# placaLeandro2.net
KiCad netlist of a schematic drawn in EAGLE
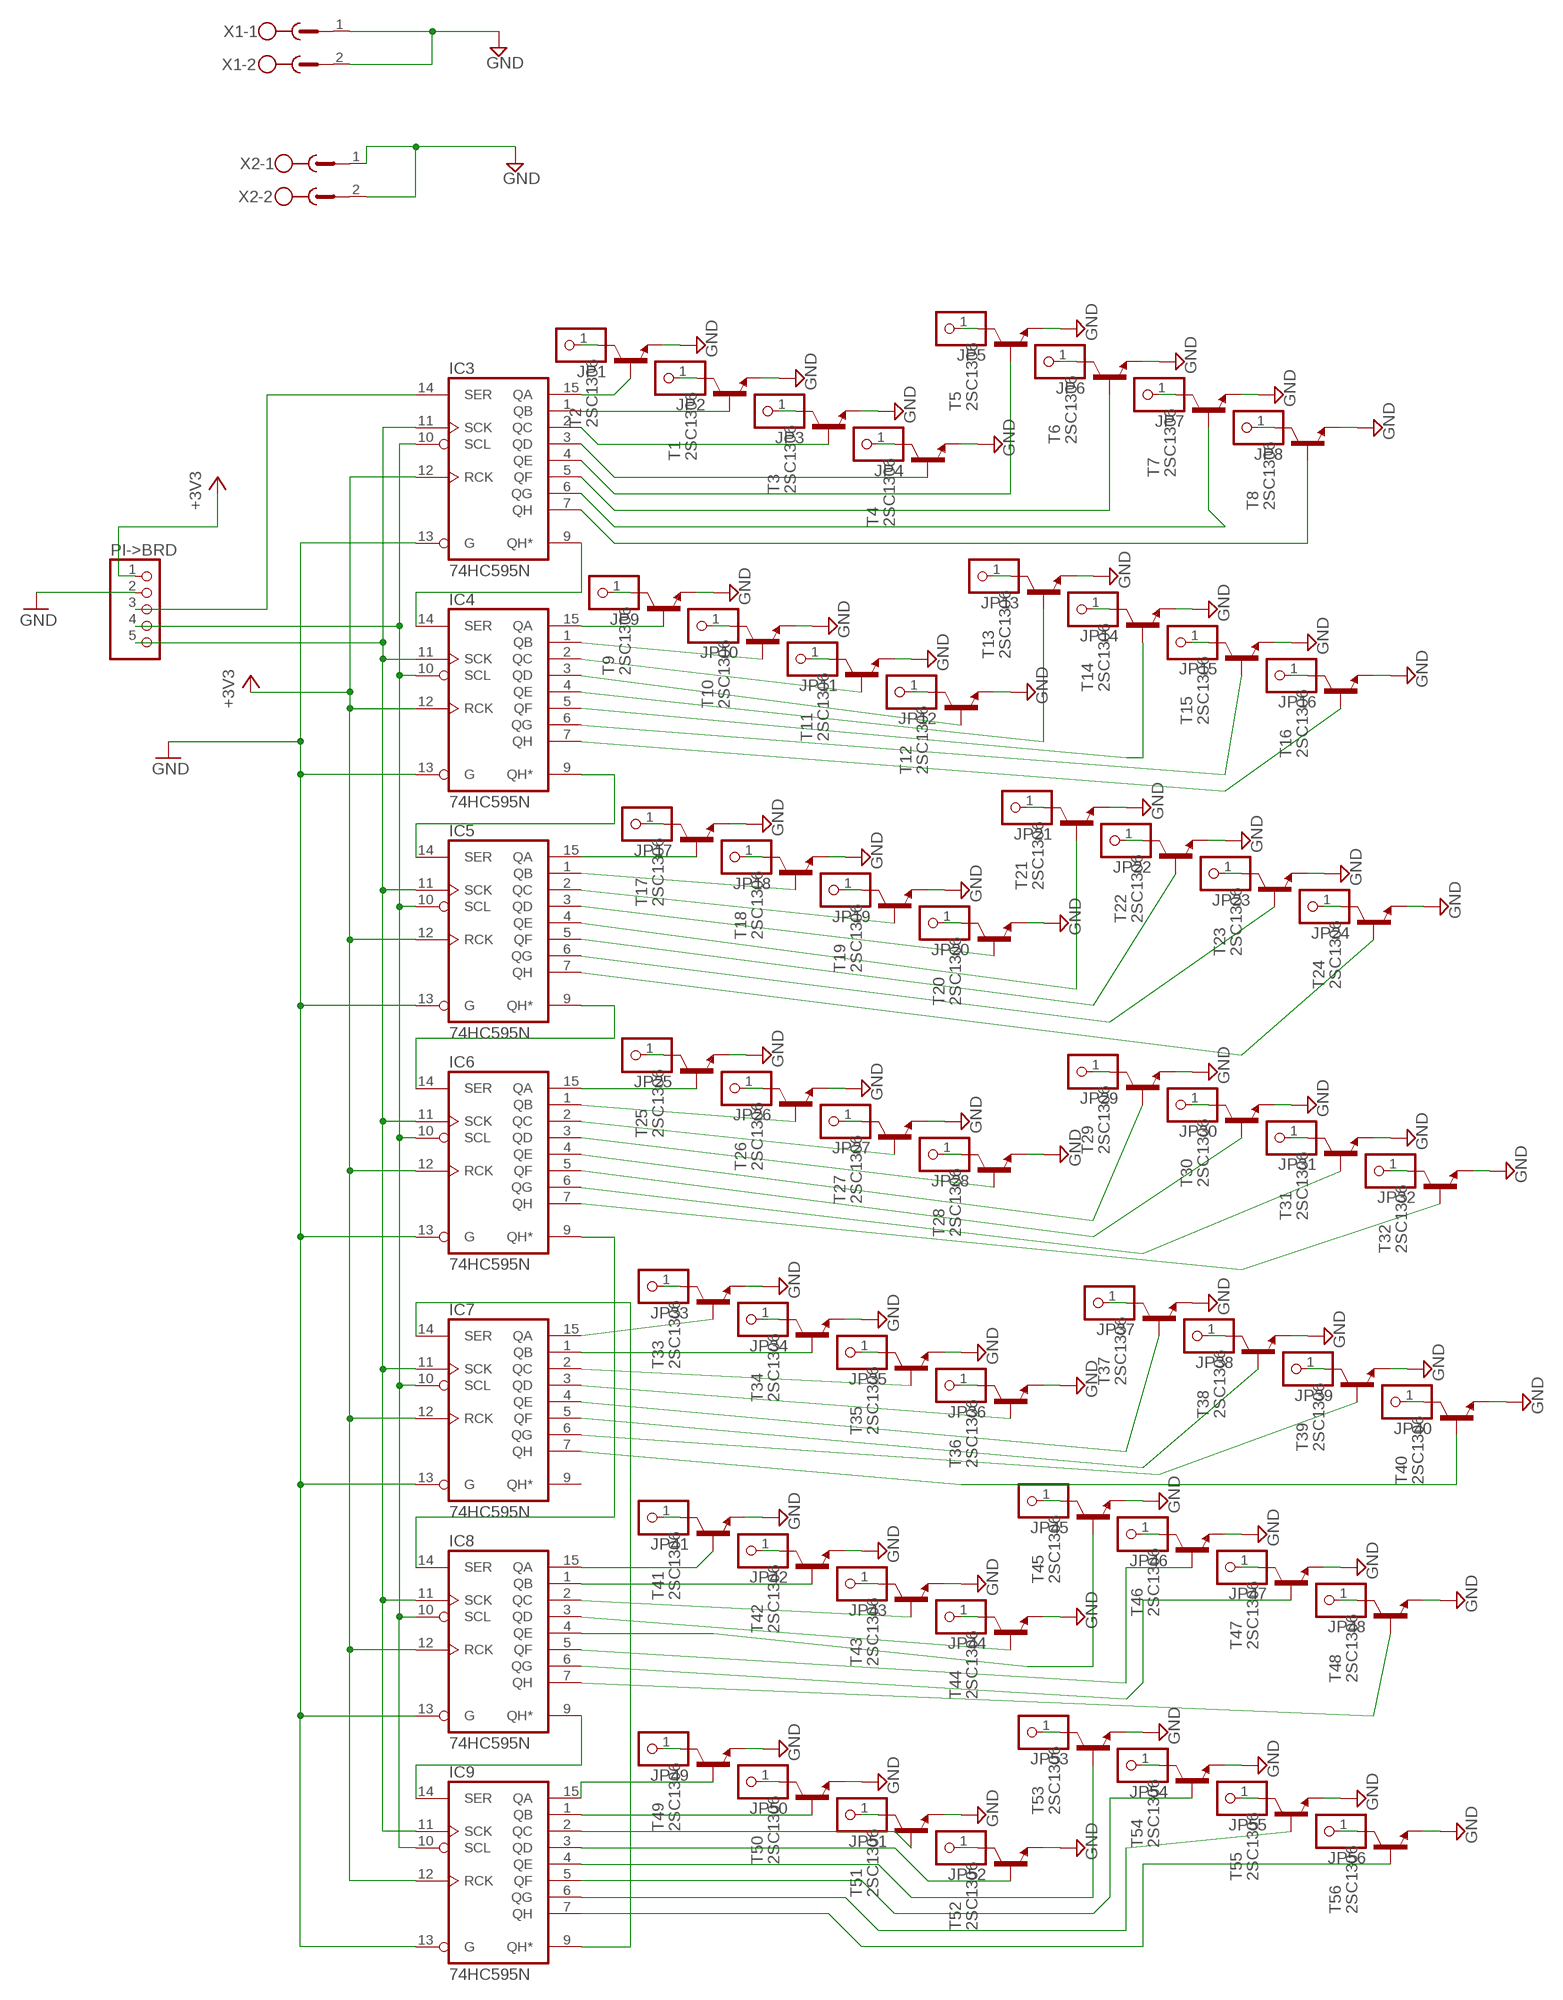
[diagram p0: schematic, sheet 1]

(export (version "E")
  (design (tool "Eeschema 10.0.6"))
  (components
    (comp (ref "IC3")
      (value "74HC595N")
      (footprint "eagle-import:DIL16")
      (libsource (lib "eagle-import") (part "74595NHC"))
    )
    (comp (ref "IC4")
      (value "74HC595N")
      (footprint "eagle-import:DIL16")
      (libsource (lib "eagle-import") (part "74595NHC"))
    )
    (comp (ref "IC5")
      (value "74HC595N")
      (footprint "eagle-import:DIL16")
      (libsource (lib "eagle-import") (part "74595NHC"))
    )
    (comp (ref "IC6")
      (value "74HC595N")
      (footprint "eagle-import:DIL16")
      (libsource (lib "eagle-import") (part "74595NHC"))
    )
    (comp (ref "IC7")
      (value "74HC595N")
      (footprint "eagle-import:DIL16")
      (libsource (lib "eagle-import") (part "74595NHC"))
    )
    (comp (ref "IC8")
      (value "74HC595N")
      (footprint "eagle-import:DIL16")
      (libsource (lib "eagle-import") (part "74595NHC"))
    )
    (comp (ref "IC9")
      (value "74HC595N")
      (footprint "eagle-import:DIL16")
      (libsource (lib "eagle-import") (part "74595NHC"))
    )
    (comp (ref "JP1")
      (value "PINHD-1X1")
      (footprint "eagle-import:1X01")
      (libsource (lib "eagle-import") (part "PINHD-1X1"))
    )
    (comp (ref "JP2")
      (value "PINHD-1X1")
      (footprint "eagle-import:1X01")
      (libsource (lib "eagle-import") (part "PINHD-1X1"))
    )
    (comp (ref "JP3")
      (value "PINHD-1X1")
      (footprint "eagle-import:1X01")
      (libsource (lib "eagle-import") (part "PINHD-1X1"))
    )
    (comp (ref "JP4")
      (value "PINHD-1X1")
      (footprint "eagle-import:1X01")
      (libsource (lib "eagle-import") (part "PINHD-1X1"))
    )
    (comp (ref "JP5")
      (value "PINHD-1X1")
      (footprint "eagle-import:1X01")
      (libsource (lib "eagle-import") (part "PINHD-1X1"))
    )
    (comp (ref "JP6")
      (value "PINHD-1X1")
      (footprint "eagle-import:1X01")
      (libsource (lib "eagle-import") (part "PINHD-1X1"))
    )
    (comp (ref "JP7")
      (value "PINHD-1X1")
      (footprint "eagle-import:1X01")
      (libsource (lib "eagle-import") (part "PINHD-1X1"))
    )
    (comp (ref "JP8")
      (value "PINHD-1X1")
      (footprint "eagle-import:1X01")
      (libsource (lib "eagle-import") (part "PINHD-1X1"))
    )
    (comp (ref "JP9")
      (value "PINHD-1X1")
      (footprint "eagle-import:1X01")
      (libsource (lib "eagle-import") (part "PINHD-1X1"))
    )
    (comp (ref "JP10")
      (value "PINHD-1X1")
      (footprint "eagle-import:1X01")
      (libsource (lib "eagle-import") (part "PINHD-1X1"))
    )
    (comp (ref "JP11")
      (value "PINHD-1X1")
      (footprint "eagle-import:1X01")
      (libsource (lib "eagle-import") (part "PINHD-1X1"))
    )
    (comp (ref "JP12")
      (value "PINHD-1X1")
      (footprint "eagle-import:1X01")
      (libsource (lib "eagle-import") (part "PINHD-1X1"))
    )
    (comp (ref "JP13")
      (value "PINHD-1X1")
      (footprint "eagle-import:1X01")
      (libsource (lib "eagle-import") (part "PINHD-1X1"))
    )
    (comp (ref "JP14")
      (value "PINHD-1X1")
      (footprint "eagle-import:1X01")
      (libsource (lib "eagle-import") (part "PINHD-1X1"))
    )
    (comp (ref "JP15")
      (value "PINHD-1X1")
      (footprint "eagle-import:1X01")
      (libsource (lib "eagle-import") (part "PINHD-1X1"))
    )
    (comp (ref "JP16")
      (value "PINHD-1X1")
      (footprint "eagle-import:1X01")
      (libsource (lib "eagle-import") (part "PINHD-1X1"))
    )
    (comp (ref "JP17")
      (value "PINHD-1X1")
      (footprint "eagle-import:1X01")
      (libsource (lib "eagle-import") (part "PINHD-1X1"))
    )
    (comp (ref "JP18")
      (value "PINHD-1X1")
      (footprint "eagle-import:1X01")
      (libsource (lib "eagle-import") (part "PINHD-1X1"))
    )
    (comp (ref "JP19")
      (value "PINHD-1X1")
      (footprint "eagle-import:1X01")
      (libsource (lib "eagle-import") (part "PINHD-1X1"))
    )
    (comp (ref "JP20")
      (value "PINHD-1X1")
      (footprint "eagle-import:1X01")
      (libsource (lib "eagle-import") (part "PINHD-1X1"))
    )
    (comp (ref "JP21")
      (value "PINHD-1X1")
      (footprint "eagle-import:1X01")
      (libsource (lib "eagle-import") (part "PINHD-1X1"))
    )
    (comp (ref "JP22")
      (value "PINHD-1X1")
      (footprint "eagle-import:1X01")
      (libsource (lib "eagle-import") (part "PINHD-1X1"))
    )
    (comp (ref "JP23")
      (value "PINHD-1X1")
      (footprint "eagle-import:1X01")
      (libsource (lib "eagle-import") (part "PINHD-1X1"))
    )
    (comp (ref "JP24")
      (value "PINHD-1X1")
      (footprint "eagle-import:1X01")
      (libsource (lib "eagle-import") (part "PINHD-1X1"))
    )
    (comp (ref "JP25")
      (value "PINHD-1X1")
      (footprint "eagle-import:1X01")
      (libsource (lib "eagle-import") (part "PINHD-1X1"))
    )
    (comp (ref "JP26")
      (value "PINHD-1X1")
      (footprint "eagle-import:1X01")
      (libsource (lib "eagle-import") (part "PINHD-1X1"))
    )
    (comp (ref "JP27")
      (value "PINHD-1X1")
      (footprint "eagle-import:1X01")
      (libsource (lib "eagle-import") (part "PINHD-1X1"))
    )
    (comp (ref "JP28")
      (value "PINHD-1X1")
      (footprint "eagle-import:1X01")
      (libsource (lib "eagle-import") (part "PINHD-1X1"))
    )
    (comp (ref "JP29")
      (value "PINHD-1X1")
      (footprint "eagle-import:1X01")
      (libsource (lib "eagle-import") (part "PINHD-1X1"))
    )
    (comp (ref "JP30")
      (value "PINHD-1X1")
      (footprint "eagle-import:1X01")
      (libsource (lib "eagle-import") (part "PINHD-1X1"))
    )
    (comp (ref "JP31")
      (value "PINHD-1X1")
      (footprint "eagle-import:1X01")
      (libsource (lib "eagle-import") (part "PINHD-1X1"))
    )
    (comp (ref "JP32")
      (value "PINHD-1X1")
      (footprint "eagle-import:1X01")
      (libsource (lib "eagle-import") (part "PINHD-1X1"))
    )
    (comp (ref "JP33")
      (value "PINHD-1X1")
      (footprint "eagle-import:1X01")
      (libsource (lib "eagle-import") (part "PINHD-1X1"))
    )
    (comp (ref "JP34")
      (value "PINHD-1X1")
      (footprint "eagle-import:1X01")
      (libsource (lib "eagle-import") (part "PINHD-1X1"))
    )
    (comp (ref "JP35")
      (value "PINHD-1X1")
      (footprint "eagle-import:1X01")
      (libsource (lib "eagle-import") (part "PINHD-1X1"))
    )
    (comp (ref "JP36")
      (value "PINHD-1X1")
      (footprint "eagle-import:1X01")
      (libsource (lib "eagle-import") (part "PINHD-1X1"))
    )
    (comp (ref "JP37")
      (value "PINHD-1X1")
      (footprint "eagle-import:1X01")
      (libsource (lib "eagle-import") (part "PINHD-1X1"))
    )
    (comp (ref "JP38")
      (value "PINHD-1X1")
      (footprint "eagle-import:1X01")
      (libsource (lib "eagle-import") (part "PINHD-1X1"))
    )
    (comp (ref "JP39")
      (value "PINHD-1X1")
      (footprint "eagle-import:1X01")
      (libsource (lib "eagle-import") (part "PINHD-1X1"))
    )
    (comp (ref "JP40")
      (value "PINHD-1X1")
      (footprint "eagle-import:1X01")
      (libsource (lib "eagle-import") (part "PINHD-1X1"))
    )
    (comp (ref "JP41")
      (value "PINHD-1X1")
      (footprint "eagle-import:1X01")
      (libsource (lib "eagle-import") (part "PINHD-1X1"))
    )
    (comp (ref "JP42")
      (value "PINHD-1X1")
      (footprint "eagle-import:1X01")
      (libsource (lib "eagle-import") (part "PINHD-1X1"))
    )
    (comp (ref "JP43")
      (value "PINHD-1X1")
      (footprint "eagle-import:1X01")
      (libsource (lib "eagle-import") (part "PINHD-1X1"))
    )
    (comp (ref "JP44")
      (value "PINHD-1X1")
      (footprint "eagle-import:1X01")
      (libsource (lib "eagle-import") (part "PINHD-1X1"))
    )
    (comp (ref "JP45")
      (value "PINHD-1X1")
      (footprint "eagle-import:1X01")
      (libsource (lib "eagle-import") (part "PINHD-1X1"))
    )
    (comp (ref "JP46")
      (value "PINHD-1X1")
      (footprint "eagle-import:1X01")
      (libsource (lib "eagle-import") (part "PINHD-1X1"))
    )
    (comp (ref "JP47")
      (value "PINHD-1X1")
      (footprint "eagle-import:1X01")
      (libsource (lib "eagle-import") (part "PINHD-1X1"))
    )
    (comp (ref "JP48")
      (value "PINHD-1X1")
      (footprint "eagle-import:1X01")
      (libsource (lib "eagle-import") (part "PINHD-1X1"))
    )
    (comp (ref "JP49")
      (value "PINHD-1X1")
      (footprint "eagle-import:1X01")
      (libsource (lib "eagle-import") (part "PINHD-1X1"))
    )
    (comp (ref "JP50")
      (value "PINHD-1X1")
      (footprint "eagle-import:1X01")
      (libsource (lib "eagle-import") (part "PINHD-1X1"))
    )
    (comp (ref "JP51")
      (value "PINHD-1X1")
      (footprint "eagle-import:1X01")
      (libsource (lib "eagle-import") (part "PINHD-1X1"))
    )
    (comp (ref "JP52")
      (value "PINHD-1X1")
      (footprint "eagle-import:1X01")
      (libsource (lib "eagle-import") (part "PINHD-1X1"))
    )
    (comp (ref "JP53")
      (value "PINHD-1X1")
      (footprint "eagle-import:1X01")
      (libsource (lib "eagle-import") (part "PINHD-1X1"))
    )
    (comp (ref "JP54")
      (value "PINHD-1X1")
      (footprint "eagle-import:1X01")
      (libsource (lib "eagle-import") (part "PINHD-1X1"))
    )
    (comp (ref "JP55")
      (value "PINHD-1X1")
      (footprint "eagle-import:1X01")
      (libsource (lib "eagle-import") (part "PINHD-1X1"))
    )
    (comp (ref "JP56")
      (value "PINHD-1X1")
      (footprint "eagle-import:1X01")
      (libsource (lib "eagle-import") (part "PINHD-1X1"))
    )
    (comp (ref "PI->BRD")
      (value "PINHD-1X5")
      (footprint "eagle-import:1X05")
      (libsource (lib "eagle-import") (part "PINHD-1X5"))
    )
    (comp (ref "T1")
      (value "2SC1306")
      (footprint "eagle-import:TO220BV")
      (libsource (lib "eagle-import") (part "2SC1306"))
    )
    (comp (ref "T2")
      (value "2SC1306")
      (footprint "eagle-import:TO220BV")
      (libsource (lib "eagle-import") (part "2SC1306"))
    )
    (comp (ref "T3")
      (value "2SC1306")
      (footprint "eagle-import:TO220BV")
      (libsource (lib "eagle-import") (part "2SC1306"))
    )
    (comp (ref "T4")
      (value "2SC1306")
      (footprint "eagle-import:TO220BV")
      (libsource (lib "eagle-import") (part "2SC1306"))
    )
    (comp (ref "T5")
      (value "2SC1306")
      (footprint "eagle-import:TO220BV")
      (libsource (lib "eagle-import") (part "2SC1306"))
    )
    (comp (ref "T6")
      (value "2SC1306")
      (footprint "eagle-import:TO220BV")
      (libsource (lib "eagle-import") (part "2SC1306"))
    )
    (comp (ref "T7")
      (value "2SC1306")
      (footprint "eagle-import:TO220BV")
      (libsource (lib "eagle-import") (part "2SC1306"))
    )
    (comp (ref "T8")
      (value "2SC1306")
      (footprint "eagle-import:TO220BV")
      (libsource (lib "eagle-import") (part "2SC1306"))
    )
    (comp (ref "T9")
      (value "2SC1306")
      (footprint "eagle-import:TO220BV")
      (libsource (lib "eagle-import") (part "2SC1306"))
    )
    (comp (ref "T10")
      (value "2SC1306")
      (footprint "eagle-import:TO220BV")
      (libsource (lib "eagle-import") (part "2SC1306"))
    )
    (comp (ref "T11")
      (value "2SC1306")
      (footprint "eagle-import:TO220BV")
      (libsource (lib "eagle-import") (part "2SC1306"))
    )
    (comp (ref "T12")
      (value "2SC1306")
      (footprint "eagle-import:TO220BV")
      (libsource (lib "eagle-import") (part "2SC1306"))
    )
    (comp (ref "T13")
      (value "2SC1306")
      (footprint "eagle-import:TO220BV")
      (libsource (lib "eagle-import") (part "2SC1306"))
    )
    (comp (ref "T14")
      (value "2SC1306")
      (footprint "eagle-import:TO220BV")
      (libsource (lib "eagle-import") (part "2SC1306"))
    )
    (comp (ref "T15")
      (value "2SC1306")
      (footprint "eagle-import:TO220BV")
      (libsource (lib "eagle-import") (part "2SC1306"))
    )
    (comp (ref "T16")
      (value "2SC1306")
      (footprint "eagle-import:TO220BV")
      (libsource (lib "eagle-import") (part "2SC1306"))
    )
    (comp (ref "T17")
      (value "2SC1306")
      (footprint "eagle-import:TO220BV")
      (libsource (lib "eagle-import") (part "2SC1306"))
    )
    (comp (ref "T18")
      (value "2SC1306")
      (footprint "eagle-import:TO220BV")
      (libsource (lib "eagle-import") (part "2SC1306"))
    )
    (comp (ref "T19")
      (value "2SC1306")
      (footprint "eagle-import:TO220BV")
      (libsource (lib "eagle-import") (part "2SC1306"))
    )
    (comp (ref "T20")
      (value "2SC1306")
      (footprint "eagle-import:TO220BV")
      (libsource (lib "eagle-import") (part "2SC1306"))
    )
    (comp (ref "T21")
      (value "2SC1306")
      (footprint "eagle-import:TO220BV")
      (libsource (lib "eagle-import") (part "2SC1306"))
    )
    (comp (ref "T22")
      (value "2SC1306")
      (footprint "eagle-import:TO220BV")
      (libsource (lib "eagle-import") (part "2SC1306"))
    )
    (comp (ref "T23")
      (value "2SC1306")
      (footprint "eagle-import:TO220BV")
      (libsource (lib "eagle-import") (part "2SC1306"))
    )
    (comp (ref "T24")
      (value "2SC1306")
      (footprint "eagle-import:TO220BV")
      (libsource (lib "eagle-import") (part "2SC1306"))
    )
    (comp (ref "T25")
      (value "2SC1306")
      (footprint "eagle-import:TO220BV")
      (libsource (lib "eagle-import") (part "2SC1306"))
    )
    (comp (ref "T26")
      (value "2SC1306")
      (footprint "eagle-import:TO220BV")
      (libsource (lib "eagle-import") (part "2SC1306"))
    )
    (comp (ref "T27")
      (value "2SC1306")
      (footprint "eagle-import:TO220BV")
      (libsource (lib "eagle-import") (part "2SC1306"))
    )
    (comp (ref "T28")
      (value "2SC1306")
      (footprint "eagle-import:TO220BV")
      (libsource (lib "eagle-import") (part "2SC1306"))
    )
    (comp (ref "T29")
      (value "2SC1306")
      (footprint "eagle-import:TO220BV")
      (libsource (lib "eagle-import") (part "2SC1306"))
    )
    (comp (ref "T30")
      (value "2SC1306")
      (footprint "eagle-import:TO220BV")
      (libsource (lib "eagle-import") (part "2SC1306"))
    )
    (comp (ref "T31")
      (value "2SC1306")
      (footprint "eagle-import:TO220BV")
      (libsource (lib "eagle-import") (part "2SC1306"))
    )
    (comp (ref "T32")
      (value "2SC1306")
      (footprint "eagle-import:TO220BV")
      (libsource (lib "eagle-import") (part "2SC1306"))
    )
    (comp (ref "T33")
      (value "2SC1306")
      (footprint "eagle-import:TO220BV")
      (libsource (lib "eagle-import") (part "2SC1306"))
    )
    (comp (ref "T34")
      (value "2SC1306")
      (footprint "eagle-import:TO220BV")
      (libsource (lib "eagle-import") (part "2SC1306"))
    )
    (comp (ref "T35")
      (value "2SC1306")
      (footprint "eagle-import:TO220BV")
      (libsource (lib "eagle-import") (part "2SC1306"))
    )
    (comp (ref "T36")
      (value "2SC1306")
      (footprint "eagle-import:TO220BV")
      (libsource (lib "eagle-import") (part "2SC1306"))
    )
    (comp (ref "T37")
      (value "2SC1306")
      (footprint "eagle-import:TO220BV")
      (libsource (lib "eagle-import") (part "2SC1306"))
    )
    (comp (ref "T38")
      (value "2SC1306")
      (footprint "eagle-import:TO220BV")
      (libsource (lib "eagle-import") (part "2SC1306"))
    )
    (comp (ref "T39")
      (value "2SC1306")
      (footprint "eagle-import:TO220BV")
      (libsource (lib "eagle-import") (part "2SC1306"))
    )
    (comp (ref "T40")
      (value "2SC1306")
      (footprint "eagle-import:TO220BV")
      (libsource (lib "eagle-import") (part "2SC1306"))
    )
    (comp (ref "T41")
      (value "2SC1306")
      (footprint "eagle-import:TO220BV")
      (libsource (lib "eagle-import") (part "2SC1306"))
    )
    (comp (ref "T42")
      (value "2SC1306")
      (footprint "eagle-import:TO220BV")
      (libsource (lib "eagle-import") (part "2SC1306"))
    )
    (comp (ref "T43")
      (value "2SC1306")
      (footprint "eagle-import:TO220BV")
      (libsource (lib "eagle-import") (part "2SC1306"))
    )
    (comp (ref "T44")
      (value "2SC1306")
      (footprint "eagle-import:TO220BV")
      (libsource (lib "eagle-import") (part "2SC1306"))
    )
    (comp (ref "T45")
      (value "2SC1306")
      (footprint "eagle-import:TO220BV")
      (libsource (lib "eagle-import") (part "2SC1306"))
    )
    (comp (ref "T46")
      (value "2SC1306")
      (footprint "eagle-import:TO220BV")
      (libsource (lib "eagle-import") (part "2SC1306"))
    )
    (comp (ref "T47")
      (value "2SC1306")
      (footprint "eagle-import:TO220BV")
      (libsource (lib "eagle-import") (part "2SC1306"))
    )
    (comp (ref "T48")
      (value "2SC1306")
      (footprint "eagle-import:TO220BV")
      (libsource (lib "eagle-import") (part "2SC1306"))
    )
    (comp (ref "T49")
      (value "2SC1306")
      (footprint "eagle-import:TO220BV")
      (libsource (lib "eagle-import") (part "2SC1306"))
    )
    (comp (ref "T50")
      (value "2SC1306")
      (footprint "eagle-import:TO220BV")
      (libsource (lib "eagle-import") (part "2SC1306"))
    )
    (comp (ref "T51")
      (value "2SC1306")
      (footprint "eagle-import:TO220BV")
      (libsource (lib "eagle-import") (part "2SC1306"))
    )
    (comp (ref "T52")
      (value "2SC1306")
      (footprint "eagle-import:TO220BV")
      (libsource (lib "eagle-import") (part "2SC1306"))
    )
    (comp (ref "T53")
      (value "2SC1306")
      (footprint "eagle-import:TO220BV")
      (libsource (lib "eagle-import") (part "2SC1306"))
    )
    (comp (ref "T54")
      (value "2SC1306")
      (footprint "eagle-import:TO220BV")
      (libsource (lib "eagle-import") (part "2SC1306"))
    )
    (comp (ref "T55")
      (value "2SC1306")
      (footprint "eagle-import:TO220BV")
      (libsource (lib "eagle-import") (part "2SC1306"))
    )
    (comp (ref "T56")
      (value "2SC1306")
      (footprint "eagle-import:TO220BV")
      (libsource (lib "eagle-import") (part "2SC1306"))
    )
    (comp (ref "X1")
      (value "MSTBV2")
      (footprint "eagle-import:MSTBV2")
      (libsource (lib "eagle-import") (part "MSTBV2"))
    )
    (comp (ref "X2")
      (value "MSTBV2")
      (footprint "eagle-import:MSTBV2")
      (libsource (lib "eagle-import") (part "MSTBV2"))
    )
  )
  (nets
    (net (code "1") (name "+3V3") (class "Default")
      (node (ref "IC3") (pin "12") (pinfunction "RCK_12") (pintype "input"))
      (node (ref "IC4") (pin "12") (pinfunction "RCK_12") (pintype "input"))
      (node (ref "IC5") (pin "12") (pinfunction "RCK_12") (pintype "input"))
      (node (ref "IC6") (pin "12") (pinfunction "RCK_12") (pintype "input"))
      (node (ref "IC7") (pin "12") (pinfunction "RCK_12") (pintype "input"))
      (node (ref "IC8") (pin "12") (pinfunction "RCK_12") (pintype "input"))
      (node (ref "IC9") (pin "12") (pinfunction "RCK_12") (pintype "input"))
      (node (ref "PI->BRD") (pin "1") (pinfunction "1_1") (pintype "passive"))
    )
    (net (code "2") (name "GND") (class "Default")
      (node (ref "IC3") (pin "13") (pinfunction "G_13") (pintype "input"))
      (node (ref "IC4") (pin "13") (pinfunction "G_13") (pintype "input"))
      (node (ref "IC5") (pin "13") (pinfunction "G_13") (pintype "input"))
      (node (ref "IC6") (pin "13") (pinfunction "G_13") (pintype "input"))
      (node (ref "IC7") (pin "13") (pinfunction "G_13") (pintype "input"))
      (node (ref "IC8") (pin "13") (pinfunction "G_13") (pintype "input"))
      (node (ref "IC9") (pin "13") (pinfunction "G_13") (pintype "input"))
      (node (ref "PI->BRD") (pin "2") (pinfunction "2_2") (pintype "passive"))
      (node (ref "T1") (pin "3") (pinfunction "E_3") (pintype "passive"))
      (node (ref "T10") (pin "3") (pinfunction "E_3") (pintype "passive"))
      (node (ref "T11") (pin "3") (pinfunction "E_3") (pintype "passive"))
      (node (ref "T12") (pin "3") (pinfunction "E_3") (pintype "passive"))
      (node (ref "T13") (pin "3") (pinfunction "E_3") (pintype "passive"))
      (node (ref "T14") (pin "3") (pinfunction "E_3") (pintype "passive"))
      (node (ref "T15") (pin "3") (pinfunction "E_3") (pintype "passive"))
      (node (ref "T16") (pin "3") (pinfunction "E_3") (pintype "passive"))
      (node (ref "T17") (pin "3") (pinfunction "E_3") (pintype "passive"))
      (node (ref "T18") (pin "3") (pinfunction "E_3") (pintype "passive"))
      (node (ref "T19") (pin "3") (pinfunction "E_3") (pintype "passive"))
      (node (ref "T2") (pin "3") (pinfunction "E_3") (pintype "passive"))
      (node (ref "T20") (pin "3") (pinfunction "E_3") (pintype "passive"))
      (node (ref "T21") (pin "3") (pinfunction "E_3") (pintype "passive"))
      (node (ref "T22") (pin "3") (pinfunction "E_3") (pintype "passive"))
      (node (ref "T23") (pin "3") (pinfunction "E_3") (pintype "passive"))
      (node (ref "T24") (pin "3") (pinfunction "E_3") (pintype "passive"))
      (node (ref "T25") (pin "3") (pinfunction "E_3") (pintype "passive"))
      (node (ref "T26") (pin "3") (pinfunction "E_3") (pintype "passive"))
      (node (ref "T27") (pin "3") (pinfunction "E_3") (pintype "passive"))
      (node (ref "T28") (pin "3") (pinfunction "E_3") (pintype "passive"))
      (node (ref "T29") (pin "3") (pinfunction "E_3") (pintype "passive"))
      (node (ref "T3") (pin "3") (pinfunction "E_3") (pintype "passive"))
      (node (ref "T30") (pin "3") (pinfunction "E_3") (pintype "passive"))
      (node (ref "T31") (pin "3") (pinfunction "E_3") (pintype "passive"))
      (node (ref "T32") (pin "3") (pinfunction "E_3") (pintype "passive"))
      (node (ref "T33") (pin "3") (pinfunction "E_3") (pintype "passive"))
      (node (ref "T34") (pin "3") (pinfunction "E_3") (pintype "passive"))
      (node (ref "T35") (pin "3") (pinfunction "E_3") (pintype "passive"))
      (node (ref "T36") (pin "3") (pinfunction "E_3") (pintype "passive"))
      (node (ref "T37") (pin "3") (pinfunction "E_3") (pintype "passive"))
      (node (ref "T38") (pin "3") (pinfunction "E_3") (pintype "passive"))
      (node (ref "T39") (pin "3") (pinfunction "E_3") (pintype "passive"))
      (node (ref "T4") (pin "3") (pinfunction "E_3") (pintype "passive"))
      (node (ref "T40") (pin "3") (pinfunction "E_3") (pintype "passive"))
      (node (ref "T41") (pin "3") (pinfunction "E_3") (pintype "passive"))
      (node (ref "T42") (pin "3") (pinfunction "E_3") (pintype "passive"))
      (node (ref "T43") (pin "3") (pinfunction "E_3") (pintype "passive"))
      (node (ref "T44") (pin "3") (pinfunction "E_3") (pintype "passive"))
      (node (ref "T45") (pin "3") (pinfunction "E_3") (pintype "passive"))
      (node (ref "T46") (pin "3") (pinfunction "E_3") (pintype "passive"))
      (node (ref "T47") (pin "3") (pinfunction "E_3") (pintype "passive"))
      (node (ref "T48") (pin "3") (pinfunction "E_3") (pintype "passive"))
      (node (ref "T49") (pin "3") (pinfunction "E_3") (pintype "passive"))
      (node (ref "T5") (pin "3") (pinfunction "E_3") (pintype "passive"))
      (node (ref "T50") (pin "3") (pinfunction "E_3") (pintype "passive"))
      (node (ref "T51") (pin "3") (pinfunction "E_3") (pintype "passive"))
      (node (ref "T52") (pin "3") (pinfunction "E_3") (pintype "passive"))
      (node (ref "T53") (pin "3") (pinfunction "E_3") (pintype "passive"))
      (node (ref "T54") (pin "3") (pinfunction "E_3") (pintype "passive"))
      (node (ref "T55") (pin "3") (pinfunction "E_3") (pintype "passive"))
      (node (ref "T56") (pin "3") (pinfunction "E_3") (pintype "passive"))
      (node (ref "T6") (pin "3") (pinfunction "E_3") (pintype "passive"))
      (node (ref "T7") (pin "3") (pinfunction "E_3") (pintype "passive"))
      (node (ref "T8") (pin "3") (pinfunction "E_3") (pintype "passive"))
      (node (ref "T9") (pin "3") (pinfunction "E_3") (pintype "passive"))
      (node (ref "X1") (pin "1") (pinfunction "SK_1") (pintype "passive"))
      (node (ref "X1") (pin "2") (pinfunction "SK_2") (pintype "passive"))
      (node (ref "X2") (pin "1") (pinfunction "SK_1") (pintype "passive"))
      (node (ref "X2") (pin "2") (pinfunction "SK_2") (pintype "passive"))
    )
    (net (code "3") (name "Net-(IC3A-QA)") (class "Default")
      (node (ref "IC3") (pin "15") (pinfunction "QA_15") (pintype "tri_state"))
      (node (ref "T2") (pin "1") (pinfunction "B_1") (pintype "passive"))
    )
    (net (code "4") (name "Net-(IC3A-QB)") (class "Default")
      (node (ref "IC3") (pin "1") (pinfunction "QB_1") (pintype "tri_state"))
      (node (ref "T1") (pin "1") (pinfunction "B_1") (pintype "passive"))
    )
    (net (code "5") (name "Net-(IC3A-QC)") (class "Default")
      (node (ref "IC3") (pin "2") (pinfunction "QC_2") (pintype "tri_state"))
      (node (ref "T3") (pin "1") (pinfunction "B_1") (pintype "passive"))
    )
    (net (code "6") (name "Net-(IC3A-QD)") (class "Default")
      (node (ref "IC3") (pin "3") (pinfunction "QD_3") (pintype "tri_state"))
      (node (ref "T4") (pin "1") (pinfunction "B_1") (pintype "passive"))
    )
    (net (code "7") (name "Net-(IC3A-QE)") (class "Default")
      (node (ref "IC3") (pin "4") (pinfunction "QE_4") (pintype "tri_state"))
      (node (ref "T5") (pin "1") (pinfunction "B_1") (pintype "passive"))
    )
    (net (code "8") (name "Net-(IC3A-QF)") (class "Default")
      (node (ref "IC3") (pin "5") (pinfunction "QF_5") (pintype "tri_state"))
      (node (ref "T6") (pin "1") (pinfunction "B_1") (pintype "passive"))
    )
    (net (code "9") (name "Net-(IC3A-QG)") (class "Default")
      (node (ref "IC3") (pin "6") (pinfunction "QG_6") (pintype "tri_state"))
      (node (ref "T7") (pin "1") (pinfunction "B_1") (pintype "passive"))
    )
    (net (code "10") (name "Net-(IC3A-QH)") (class "Default")
      (node (ref "IC3") (pin "7") (pinfunction "QH_7") (pintype "tri_state"))
      (node (ref "T8") (pin "1") (pinfunction "B_1") (pintype "passive"))
    )
    (net (code "11") (name "Net-(IC3A-QH*)") (class "Default")
      (node (ref "IC3") (pin "9") (pinfunction "QH*_9") (pintype "tri_state"))
      (node (ref "IC4") (pin "14") (pinfunction "SER_14") (pintype "input"))
    )
    (net (code "12") (name "Net-(IC3A-SCK)") (class "Default")
      (node (ref "IC3") (pin "11") (pinfunction "SCK_11") (pintype "input"))
      (node (ref "IC4") (pin "11") (pinfunction "SCK_11") (pintype "input"))
      (node (ref "IC5") (pin "11") (pinfunction "SCK_11") (pintype "input"))
      (node (ref "IC6") (pin "11") (pinfunction "SCK_11") (pintype "input"))
      (node (ref "IC7") (pin "11") (pinfunction "SCK_11") (pintype "input"))
      (node (ref "IC8") (pin "11") (pinfunction "SCK_11") (pintype "input"))
      (node (ref "IC9") (pin "11") (pinfunction "SCK_11") (pintype "input"))
      (node (ref "PI->BRD") (pin "5") (pinfunction "5_5") (pintype "passive"))
    )
    (net (code "13") (name "Net-(IC3A-SCL)") (class "Default")
      (node (ref "IC3") (pin "10") (pinfunction "SCL_10") (pintype "input"))
      (node (ref "IC4") (pin "10") (pinfunction "SCL_10") (pintype "input"))
      (node (ref "IC5") (pin "10") (pinfunction "SCL_10") (pintype "input"))
      (node (ref "IC6") (pin "10") (pinfunction "SCL_10") (pintype "input"))
      (node (ref "IC7") (pin "10") (pinfunction "SCL_10") (pintype "input"))
      (node (ref "IC8") (pin "10") (pinfunction "SCL_10") (pintype "input"))
      (node (ref "IC9") (pin "10") (pinfunction "SCL_10") (pintype "input"))
      (node (ref "PI->BRD") (pin "4") (pinfunction "4_4") (pintype "passive"))
    )
    (net (code "14") (name "Net-(IC3A-SER)") (class "Default")
      (node (ref "IC3") (pin "14") (pinfunction "SER_14") (pintype "input"))
      (node (ref "PI->BRD") (pin "3") (pinfunction "3_3") (pintype "passive"))
    )
    (net (code "15") (name "Net-(IC4A-QA)") (class "Default")
      (node (ref "IC4") (pin "15") (pinfunction "QA_15") (pintype "tri_state"))
      (node (ref "T9") (pin "1") (pinfunction "B_1") (pintype "passive"))
    )
    (net (code "16") (name "Net-(IC4A-QB)") (class "Default")
      (node (ref "IC4") (pin "1") (pinfunction "QB_1") (pintype "tri_state"))
      (node (ref "T10") (pin "1") (pinfunction "B_1") (pintype "passive"))
    )
    (net (code "17") (name "Net-(IC4A-QC)") (class "Default")
      (node (ref "IC4") (pin "2") (pinfunction "QC_2") (pintype "tri_state"))
      (node (ref "T11") (pin "1") (pinfunction "B_1") (pintype "passive"))
    )
    (net (code "18") (name "Net-(IC4A-QD)") (class "Default")
      (node (ref "IC4") (pin "3") (pinfunction "QD_3") (pintype "tri_state"))
      (node (ref "T12") (pin "1") (pinfunction "B_1") (pintype "passive"))
    )
    (net (code "19") (name "Net-(IC4A-QE)") (class "Default")
      (node (ref "IC4") (pin "4") (pinfunction "QE_4") (pintype "tri_state"))
      (node (ref "T13") (pin "1") (pinfunction "B_1") (pintype "passive"))
    )
    (net (code "20") (name "Net-(IC4A-QF)") (class "Default")
      (node (ref "IC4") (pin "5") (pinfunction "QF_5") (pintype "tri_state"))
      (node (ref "T14") (pin "1") (pinfunction "B_1") (pintype "passive"))
    )
    (net (code "21") (name "Net-(IC4A-QG)") (class "Default")
      (node (ref "IC4") (pin "6") (pinfunction "QG_6") (pintype "tri_state"))
      (node (ref "T15") (pin "1") (pinfunction "B_1") (pintype "passive"))
    )
    (net (code "22") (name "Net-(IC4A-QH)") (class "Default")
      (node (ref "IC4") (pin "7") (pinfunction "QH_7") (pintype "tri_state"))
      (node (ref "T16") (pin "1") (pinfunction "B_1") (pintype "passive"))
    )
    (net (code "23") (name "Net-(IC4A-QH*)") (class "Default")
      (node (ref "IC4") (pin "9") (pinfunction "QH*_9") (pintype "tri_state"))
      (node (ref "IC5") (pin "14") (pinfunction "SER_14") (pintype "input"))
    )
    (net (code "24") (name "Net-(IC5A-QA)") (class "Default")
      (node (ref "IC5") (pin "15") (pinfunction "QA_15") (pintype "tri_state"))
      (node (ref "T17") (pin "1") (pinfunction "B_1") (pintype "passive"))
    )
    (net (code "25") (name "Net-(IC5A-QB)") (class "Default")
      (node (ref "IC5") (pin "1") (pinfunction "QB_1") (pintype "tri_state"))
      (node (ref "T18") (pin "1") (pinfunction "B_1") (pintype "passive"))
    )
    (net (code "26") (name "Net-(IC5A-QC)") (class "Default")
      (node (ref "IC5") (pin "2") (pinfunction "QC_2") (pintype "tri_state"))
      (node (ref "T19") (pin "1") (pinfunction "B_1") (pintype "passive"))
    )
    (net (code "27") (name "Net-(IC5A-QD)") (class "Default")
      (node (ref "IC5") (pin "3") (pinfunction "QD_3") (pintype "tri_state"))
      (node (ref "T20") (pin "1") (pinfunction "B_1") (pintype "passive"))
    )
    (net (code "28") (name "Net-(IC5A-QE)") (class "Default")
      (node (ref "IC5") (pin "4") (pinfunction "QE_4") (pintype "tri_state"))
      (node (ref "T21") (pin "1") (pinfunction "B_1") (pintype "passive"))
    )
    (net (code "29") (name "Net-(IC5A-QF)") (class "Default")
      (node (ref "IC5") (pin "5") (pinfunction "QF_5") (pintype "tri_state"))
      (node (ref "T22") (pin "1") (pinfunction "B_1") (pintype "passive"))
    )
    (net (code "30") (name "Net-(IC5A-QG)") (class "Default")
      (node (ref "IC5") (pin "6") (pinfunction "QG_6") (pintype "tri_state"))
      (node (ref "T23") (pin "1") (pinfunction "B_1") (pintype "passive"))
    )
    (net (code "31") (name "Net-(IC5A-QH)") (class "Default")
      (node (ref "IC5") (pin "7") (pinfunction "QH_7") (pintype "tri_state"))
      (node (ref "T24") (pin "1") (pinfunction "B_1") (pintype "passive"))
    )
    (net (code "32") (name "Net-(IC5A-QH*)") (class "Default")
      (node (ref "IC5") (pin "9") (pinfunction "QH*_9") (pintype "tri_state"))
      (node (ref "IC6") (pin "14") (pinfunction "SER_14") (pintype "input"))
    )
    (net (code "33") (name "Net-(IC6A-QA)") (class "Default")
      (node (ref "IC6") (pin "15") (pinfunction "QA_15") (pintype "tri_state"))
      (node (ref "T25") (pin "1") (pinfunction "B_1") (pintype "passive"))
    )
    (net (code "34") (name "Net-(IC6A-QB)") (class "Default")
      (node (ref "IC6") (pin "1") (pinfunction "QB_1") (pintype "tri_state"))
      (node (ref "T26") (pin "1") (pinfunction "B_1") (pintype "passive"))
    )
    (net (code "35") (name "Net-(IC6A-QC)") (class "Default")
      (node (ref "IC6") (pin "2") (pinfunction "QC_2") (pintype "tri_state"))
      (node (ref "T27") (pin "1") (pinfunction "B_1") (pintype "passive"))
    )
    (net (code "36") (name "Net-(IC6A-QD)") (class "Default")
      (node (ref "IC6") (pin "3") (pinfunction "QD_3") (pintype "tri_state"))
      (node (ref "T28") (pin "1") (pinfunction "B_1") (pintype "passive"))
    )
    (net (code "37") (name "Net-(IC6A-QE)") (class "Default")
      (node (ref "IC6") (pin "4") (pinfunction "QE_4") (pintype "tri_state"))
      (node (ref "T29") (pin "1") (pinfunction "B_1") (pintype "passive"))
    )
    (net (code "38") (name "Net-(IC6A-QF)") (class "Default")
      (node (ref "IC6") (pin "5") (pinfunction "QF_5") (pintype "tri_state"))
      (node (ref "T30") (pin "1") (pinfunction "B_1") (pintype "passive"))
    )
    (net (code "39") (name "Net-(IC6A-QG)") (class "Default")
      (node (ref "IC6") (pin "6") (pinfunction "QG_6") (pintype "tri_state"))
      (node (ref "T31") (pin "1") (pinfunction "B_1") (pintype "passive"))
    )
    (net (code "40") (name "Net-(IC6A-QH)") (class "Default")
      (node (ref "IC6") (pin "7") (pinfunction "QH_7") (pintype "tri_state"))
      (node (ref "T32") (pin "1") (pinfunction "B_1") (pintype "passive"))
    )
    (net (code "41") (name "Net-(IC6A-QH*)") (class "Default")
      (node (ref "IC6") (pin "9") (pinfunction "QH*_9") (pintype "tri_state"))
      (node (ref "IC8") (pin "14") (pinfunction "SER_14") (pintype "input"))
    )
    (net (code "42") (name "Net-(IC7A-QA)") (class "Default")
      (node (ref "IC7") (pin "15") (pinfunction "QA_15") (pintype "tri_state"))
      (node (ref "T33") (pin "1") (pinfunction "B_1") (pintype "passive"))
    )
    (net (code "43") (name "Net-(IC7A-QB)") (class "Default")
      (node (ref "IC7") (pin "1") (pinfunction "QB_1") (pintype "tri_state"))
      (node (ref "T34") (pin "1") (pinfunction "B_1") (pintype "passive"))
    )
    (net (code "44") (name "Net-(IC7A-QC)") (class "Default")
      (node (ref "IC7") (pin "2") (pinfunction "QC_2") (pintype "tri_state"))
      (node (ref "T35") (pin "1") (pinfunction "B_1") (pintype "passive"))
    )
    (net (code "45") (name "Net-(IC7A-QD)") (class "Default")
      (node (ref "IC7") (pin "3") (pinfunction "QD_3") (pintype "tri_state"))
      (node (ref "T36") (pin "1") (pinfunction "B_1") (pintype "passive"))
    )
    (net (code "46") (name "Net-(IC7A-QE)") (class "Default")
      (node (ref "IC7") (pin "4") (pinfunction "QE_4") (pintype "tri_state"))
      (node (ref "T37") (pin "1") (pinfunction "B_1") (pintype "passive"))
    )
    (net (code "47") (name "Net-(IC7A-QF)") (class "Default")
      (node (ref "IC7") (pin "5") (pinfunction "QF_5") (pintype "tri_state"))
      (node (ref "T38") (pin "1") (pinfunction "B_1") (pintype "passive"))
    )
    (net (code "48") (name "Net-(IC7A-QG)") (class "Default")
      (node (ref "IC7") (pin "6") (pinfunction "QG_6") (pintype "tri_state"))
      (node (ref "T39") (pin "1") (pinfunction "B_1") (pintype "passive"))
    )
    (net (code "49") (name "Net-(IC7A-QH)") (class "Default")
      (node (ref "IC7") (pin "7") (pinfunction "QH_7") (pintype "tri_state"))
      (node (ref "T40") (pin "1") (pinfunction "B_1") (pintype "passive"))
    )
    (net (code "50") (name "Net-(IC7A-SER)") (class "Default")
      (node (ref "IC7") (pin "14") (pinfunction "SER_14") (pintype "input"))
      (node (ref "IC9") (pin "9") (pinfunction "QH*_9") (pintype "tri_state"))
    )
    (net (code "51") (name "Net-(IC8A-QA)") (class "Default")
      (node (ref "IC8") (pin "15") (pinfunction "QA_15") (pintype "tri_state"))
      (node (ref "T41") (pin "1") (pinfunction "B_1") (pintype "passive"))
    )
    (net (code "52") (name "Net-(IC8A-QB)") (class "Default")
      (node (ref "IC8") (pin "1") (pinfunction "QB_1") (pintype "tri_state"))
      (node (ref "T42") (pin "1") (pinfunction "B_1") (pintype "passive"))
    )
    (net (code "53") (name "Net-(IC8A-QC)") (class "Default")
      (node (ref "IC8") (pin "2") (pinfunction "QC_2") (pintype "tri_state"))
      (node (ref "T43") (pin "1") (pinfunction "B_1") (pintype "passive"))
    )
    (net (code "54") (name "Net-(IC8A-QD)") (class "Default")
      (node (ref "IC8") (pin "3") (pinfunction "QD_3") (pintype "tri_state"))
      (node (ref "T44") (pin "1") (pinfunction "B_1") (pintype "passive"))
    )
    (net (code "55") (name "Net-(IC8A-QE)") (class "Default")
      (node (ref "IC8") (pin "4") (pinfunction "QE_4") (pintype "tri_state"))
      (node (ref "T45") (pin "1") (pinfunction "B_1") (pintype "passive"))
    )
    (net (code "56") (name "Net-(IC8A-QF)") (class "Default")
      (node (ref "IC8") (pin "5") (pinfunction "QF_5") (pintype "tri_state"))
      (node (ref "T46") (pin "1") (pinfunction "B_1") (pintype "passive"))
    )
    (net (code "57") (name "Net-(IC8A-QG)") (class "Default")
      (node (ref "IC8") (pin "6") (pinfunction "QG_6") (pintype "tri_state"))
      (node (ref "T47") (pin "1") (pinfunction "B_1") (pintype "passive"))
    )
    (net (code "58") (name "Net-(IC8A-QH)") (class "Default")
      (node (ref "IC8") (pin "7") (pinfunction "QH_7") (pintype "tri_state"))
      (node (ref "T48") (pin "1") (pinfunction "B_1") (pintype "passive"))
    )
    (net (code "59") (name "Net-(IC8A-QH*)") (class "Default")
      (node (ref "IC8") (pin "9") (pinfunction "QH*_9") (pintype "tri_state"))
      (node (ref "IC9") (pin "14") (pinfunction "SER_14") (pintype "input"))
    )
    (net (code "60") (name "Net-(IC9A-QA)") (class "Default")
      (node (ref "IC9") (pin "15") (pinfunction "QA_15") (pintype "tri_state"))
      (node (ref "T49") (pin "1") (pinfunction "B_1") (pintype "passive"))
    )
    (net (code "61") (name "Net-(IC9A-QB)") (class "Default")
      (node (ref "IC9") (pin "1") (pinfunction "QB_1") (pintype "tri_state"))
      (node (ref "T50") (pin "1") (pinfunction "B_1") (pintype "passive"))
    )
    (net (code "62") (name "Net-(IC9A-QC)") (class "Default")
      (node (ref "IC9") (pin "2") (pinfunction "QC_2") (pintype "tri_state"))
      (node (ref "T51") (pin "1") (pinfunction "B_1") (pintype "passive"))
    )
    (net (code "63") (name "Net-(IC9A-QD)") (class "Default")
      (node (ref "IC9") (pin "3") (pinfunction "QD_3") (pintype "tri_state"))
      (node (ref "T52") (pin "1") (pinfunction "B_1") (pintype "passive"))
    )
    (net (code "64") (name "Net-(IC9A-QE)") (class "Default")
      (node (ref "IC9") (pin "4") (pinfunction "QE_4") (pintype "tri_state"))
      (node (ref "T53") (pin "1") (pinfunction "B_1") (pintype "passive"))
    )
    (net (code "65") (name "Net-(IC9A-QF)") (class "Default")
      (node (ref "IC9") (pin "5") (pinfunction "QF_5") (pintype "tri_state"))
      (node (ref "T54") (pin "1") (pinfunction "B_1") (pintype "passive"))
    )
    (net (code "66") (name "Net-(IC9A-QG)") (class "Default")
      (node (ref "IC9") (pin "6") (pinfunction "QG_6") (pintype "tri_state"))
      (node (ref "T55") (pin "1") (pinfunction "B_1") (pintype "passive"))
    )
    (net (code "67") (name "Net-(IC9A-QH)") (class "Default")
      (node (ref "IC9") (pin "7") (pinfunction "QH_7") (pintype "tri_state"))
      (node (ref "T56") (pin "1") (pinfunction "B_1") (pintype "passive"))
    )
    (net (code "68") (name "Net-(T1-C)") (class "Default")
      (node (ref "JP2") (pin "1") (pinfunction "1_1") (pintype "passive"))
      (node (ref "T1") (pin "2") (pinfunction "C_2") (pintype "passive"))
    )
    (net (code "69") (name "Net-(T2-C)") (class "Default")
      (node (ref "JP1") (pin "1") (pinfunction "1_1") (pintype "passive"))
      (node (ref "T2") (pin "2") (pinfunction "C_2") (pintype "passive"))
    )
    (net (code "70") (name "Net-(T3-C)") (class "Default")
      (node (ref "JP3") (pin "1") (pinfunction "1_1") (pintype "passive"))
      (node (ref "T3") (pin "2") (pinfunction "C_2") (pintype "passive"))
    )
    (net (code "71") (name "Net-(T4-C)") (class "Default")
      (node (ref "JP4") (pin "1") (pinfunction "1_1") (pintype "passive"))
      (node (ref "T4") (pin "2") (pinfunction "C_2") (pintype "passive"))
    )
    (net (code "72") (name "Net-(T5-C)") (class "Default")
      (node (ref "JP5") (pin "1") (pinfunction "1_1") (pintype "passive"))
      (node (ref "T5") (pin "2") (pinfunction "C_2") (pintype "passive"))
    )
    (net (code "73") (name "Net-(T6-C)") (class "Default")
      (node (ref "JP6") (pin "1") (pinfunction "1_1") (pintype "passive"))
      (node (ref "T6") (pin "2") (pinfunction "C_2") (pintype "passive"))
    )
    (net (code "74") (name "Net-(T7-C)") (class "Default")
      (node (ref "JP7") (pin "1") (pinfunction "1_1") (pintype "passive"))
      (node (ref "T7") (pin "2") (pinfunction "C_2") (pintype "passive"))
    )
    (net (code "75") (name "Net-(T8-C)") (class "Default")
      (node (ref "JP8") (pin "1") (pinfunction "1_1") (pintype "passive"))
      (node (ref "T8") (pin "2") (pinfunction "C_2") (pintype "passive"))
    )
    (net (code "76") (name "Net-(T9-C)") (class "Default")
      (node (ref "JP9") (pin "1") (pinfunction "1_1") (pintype "passive"))
      (node (ref "T9") (pin "2") (pinfunction "C_2") (pintype "passive"))
    )
    (net (code "77") (name "Net-(T10-C)") (class "Default")
      (node (ref "JP10") (pin "1") (pinfunction "1_1") (pintype "passive"))
      (node (ref "T10") (pin "2") (pinfunction "C_2") (pintype "passive"))
    )
    (net (code "78") (name "Net-(T11-C)") (class "Default")
      (node (ref "JP11") (pin "1") (pinfunction "1_1") (pintype "passive"))
      (node (ref "T11") (pin "2") (pinfunction "C_2") (pintype "passive"))
    )
    (net (code "79") (name "Net-(T12-C)") (class "Default")
      (node (ref "JP12") (pin "1") (pinfunction "1_1") (pintype "passive"))
      (node (ref "T12") (pin "2") (pinfunction "C_2") (pintype "passive"))
    )
    (net (code "80") (name "Net-(T13-C)") (class "Default")
      (node (ref "JP13") (pin "1") (pinfunction "1_1") (pintype "passive"))
      (node (ref "T13") (pin "2") (pinfunction "C_2") (pintype "passive"))
    )
    (net (code "81") (name "Net-(T14-C)") (class "Default")
      (node (ref "JP14") (pin "1") (pinfunction "1_1") (pintype "passive"))
      (node (ref "T14") (pin "2") (pinfunction "C_2") (pintype "passive"))
    )
    (net (code "82") (name "Net-(T15-C)") (class "Default")
      (node (ref "JP15") (pin "1") (pinfunction "1_1") (pintype "passive"))
      (node (ref "T15") (pin "2") (pinfunction "C_2") (pintype "passive"))
    )
    (net (code "83") (name "Net-(T16-C)") (class "Default")
      (node (ref "JP16") (pin "1") (pinfunction "1_1") (pintype "passive"))
      (node (ref "T16") (pin "2") (pinfunction "C_2") (pintype "passive"))
    )
    (net (code "84") (name "Net-(T17-C)") (class "Default")
      (node (ref "JP17") (pin "1") (pinfunction "1_1") (pintype "passive"))
      (node (ref "T17") (pin "2") (pinfunction "C_2") (pintype "passive"))
    )
    (net (code "85") (name "Net-(T18-C)") (class "Default")
      (node (ref "JP18") (pin "1") (pinfunction "1_1") (pintype "passive"))
      (node (ref "T18") (pin "2") (pinfunction "C_2") (pintype "passive"))
    )
    (net (code "86") (name "Net-(T19-C)") (class "Default")
      (node (ref "JP19") (pin "1") (pinfunction "1_1") (pintype "passive"))
      (node (ref "T19") (pin "2") (pinfunction "C_2") (pintype "passive"))
    )
    (net (code "87") (name "Net-(T20-C)") (class "Default")
      (node (ref "JP20") (pin "1") (pinfunction "1_1") (pintype "passive"))
      (node (ref "T20") (pin "2") (pinfunction "C_2") (pintype "passive"))
    )
    (net (code "88") (name "Net-(T21-C)") (class "Default")
      (node (ref "JP21") (pin "1") (pinfunction "1_1") (pintype "passive"))
      (node (ref "T21") (pin "2") (pinfunction "C_2") (pintype "passive"))
    )
    (net (code "89") (name "Net-(T22-C)") (class "Default")
      (node (ref "JP22") (pin "1") (pinfunction "1_1") (pintype "passive"))
      (node (ref "T22") (pin "2") (pinfunction "C_2") (pintype "passive"))
    )
    (net (code "90") (name "Net-(T23-C)") (class "Default")
      (node (ref "JP23") (pin "1") (pinfunction "1_1") (pintype "passive"))
      (node (ref "T23") (pin "2") (pinfunction "C_2") (pintype "passive"))
    )
    (net (code "91") (name "Net-(T24-C)") (class "Default")
      (node (ref "JP24") (pin "1") (pinfunction "1_1") (pintype "passive"))
      (node (ref "T24") (pin "2") (pinfunction "C_2") (pintype "passive"))
    )
    (net (code "92") (name "Net-(T25-C)") (class "Default")
      (node (ref "JP25") (pin "1") (pinfunction "1_1") (pintype "passive"))
      (node (ref "T25") (pin "2") (pinfunction "C_2") (pintype "passive"))
    )
    (net (code "93") (name "Net-(T26-C)") (class "Default")
      (node (ref "JP26") (pin "1") (pinfunction "1_1") (pintype "passive"))
      (node (ref "T26") (pin "2") (pinfunction "C_2") (pintype "passive"))
    )
    (net (code "94") (name "Net-(T27-C)") (class "Default")
      (node (ref "JP27") (pin "1") (pinfunction "1_1") (pintype "passive"))
      (node (ref "T27") (pin "2") (pinfunction "C_2") (pintype "passive"))
    )
    (net (code "95") (name "Net-(T28-C)") (class "Default")
      (node (ref "JP28") (pin "1") (pinfunction "1_1") (pintype "passive"))
      (node (ref "T28") (pin "2") (pinfunction "C_2") (pintype "passive"))
    )
    (net (code "96") (name "Net-(T29-C)") (class "Default")
      (node (ref "JP29") (pin "1") (pinfunction "1_1") (pintype "passive"))
      (node (ref "T29") (pin "2") (pinfunction "C_2") (pintype "passive"))
    )
    (net (code "97") (name "Net-(T30-C)") (class "Default")
      (node (ref "JP30") (pin "1") (pinfunction "1_1") (pintype "passive"))
      (node (ref "T30") (pin "2") (pinfunction "C_2") (pintype "passive"))
    )
    (net (code "98") (name "Net-(T31-C)") (class "Default")
      (node (ref "JP31") (pin "1") (pinfunction "1_1") (pintype "passive"))
      (node (ref "T31") (pin "2") (pinfunction "C_2") (pintype "passive"))
    )
    (net (code "99") (name "Net-(T32-C)") (class "Default")
      (node (ref "JP32") (pin "1") (pinfunction "1_1") (pintype "passive"))
      (node (ref "T32") (pin "2") (pinfunction "C_2") (pintype "passive"))
    )
    (net (code "100") (name "Net-(T33-C)") (class "Default")
      (node (ref "JP33") (pin "1") (pinfunction "1_1") (pintype "passive"))
      (node (ref "T33") (pin "2") (pinfunction "C_2") (pintype "passive"))
    )
    (net (code "101") (name "Net-(T34-C)") (class "Default")
      (node (ref "JP34") (pin "1") (pinfunction "1_1") (pintype "passive"))
      (node (ref "T34") (pin "2") (pinfunction "C_2") (pintype "passive"))
    )
    (net (code "102") (name "Net-(T35-C)") (class "Default")
      (node (ref "JP35") (pin "1") (pinfunction "1_1") (pintype "passive"))
      (node (ref "T35") (pin "2") (pinfunction "C_2") (pintype "passive"))
    )
    (net (code "103") (name "Net-(T36-C)") (class "Default")
      (node (ref "JP36") (pin "1") (pinfunction "1_1") (pintype "passive"))
      (node (ref "T36") (pin "2") (pinfunction "C_2") (pintype "passive"))
    )
    (net (code "104") (name "Net-(T37-C)") (class "Default")
      (node (ref "JP37") (pin "1") (pinfunction "1_1") (pintype "passive"))
      (node (ref "T37") (pin "2") (pinfunction "C_2") (pintype "passive"))
    )
    (net (code "105") (name "Net-(T38-C)") (class "Default")
      (node (ref "JP38") (pin "1") (pinfunction "1_1") (pintype "passive"))
      (node (ref "T38") (pin "2") (pinfunction "C_2") (pintype "passive"))
    )
    (net (code "106") (name "Net-(T39-C)") (class "Default")
      (node (ref "JP39") (pin "1") (pinfunction "1_1") (pintype "passive"))
      (node (ref "T39") (pin "2") (pinfunction "C_2") (pintype "passive"))
    )
    (net (code "107") (name "Net-(T40-C)") (class "Default")
      (node (ref "JP40") (pin "1") (pinfunction "1_1") (pintype "passive"))
      (node (ref "T40") (pin "2") (pinfunction "C_2") (pintype "passive"))
    )
    (net (code "108") (name "Net-(T41-C)") (class "Default")
      (node (ref "JP41") (pin "1") (pinfunction "1_1") (pintype "passive"))
      (node (ref "T41") (pin "2") (pinfunction "C_2") (pintype "passive"))
    )
    (net (code "109") (name "Net-(T42-C)") (class "Default")
      (node (ref "JP42") (pin "1") (pinfunction "1_1") (pintype "passive"))
      (node (ref "T42") (pin "2") (pinfunction "C_2") (pintype "passive"))
    )
    (net (code "110") (name "Net-(T43-C)") (class "Default")
      (node (ref "JP43") (pin "1") (pinfunction "1_1") (pintype "passive"))
      (node (ref "T43") (pin "2") (pinfunction "C_2") (pintype "passive"))
    )
    (net (code "111") (name "Net-(T44-C)") (class "Default")
      (node (ref "JP44") (pin "1") (pinfunction "1_1") (pintype "passive"))
      (node (ref "T44") (pin "2") (pinfunction "C_2") (pintype "passive"))
    )
    (net (code "112") (name "Net-(T45-C)") (class "Default")
      (node (ref "JP45") (pin "1") (pinfunction "1_1") (pintype "passive"))
      (node (ref "T45") (pin "2") (pinfunction "C_2") (pintype "passive"))
    )
    (net (code "113") (name "Net-(T46-C)") (class "Default")
      (node (ref "JP46") (pin "1") (pinfunction "1_1") (pintype "passive"))
      (node (ref "T46") (pin "2") (pinfunction "C_2") (pintype "passive"))
    )
    (net (code "114") (name "Net-(T47-C)") (class "Default")
      (node (ref "JP47") (pin "1") (pinfunction "1_1") (pintype "passive"))
      (node (ref "T47") (pin "2") (pinfunction "C_2") (pintype "passive"))
    )
    (net (code "115") (name "Net-(T48-C)") (class "Default")
      (node (ref "JP48") (pin "1") (pinfunction "1_1") (pintype "passive"))
      (node (ref "T48") (pin "2") (pinfunction "C_2") (pintype "passive"))
    )
    (net (code "116") (name "Net-(T49-C)") (class "Default")
      (node (ref "JP49") (pin "1") (pinfunction "1_1") (pintype "passive"))
      (node (ref "T49") (pin "2") (pinfunction "C_2") (pintype "passive"))
    )
    (net (code "117") (name "Net-(T50-C)") (class "Default")
      (node (ref "JP50") (pin "1") (pinfunction "1_1") (pintype "passive"))
      (node (ref "T50") (pin "2") (pinfunction "C_2") (pintype "passive"))
    )
    (net (code "118") (name "Net-(T51-C)") (class "Default")
      (node (ref "JP51") (pin "1") (pinfunction "1_1") (pintype "passive"))
      (node (ref "T51") (pin "2") (pinfunction "C_2") (pintype "passive"))
    )
    (net (code "119") (name "Net-(T52-C)") (class "Default")
      (node (ref "JP52") (pin "1") (pinfunction "1_1") (pintype "passive"))
      (node (ref "T52") (pin "2") (pinfunction "C_2") (pintype "passive"))
    )
    (net (code "120") (name "Net-(T53-C)") (class "Default")
      (node (ref "JP53") (pin "1") (pinfunction "1_1") (pintype "passive"))
      (node (ref "T53") (pin "2") (pinfunction "C_2") (pintype "passive"))
    )
    (net (code "121") (name "Net-(T54-C)") (class "Default")
      (node (ref "JP54") (pin "1") (pinfunction "1_1") (pintype "passive"))
      (node (ref "T54") (pin "2") (pinfunction "C_2") (pintype "passive"))
    )
    (net (code "122") (name "Net-(T55-C)") (class "Default")
      (node (ref "JP55") (pin "1") (pinfunction "1_1") (pintype "passive"))
      (node (ref "T55") (pin "2") (pinfunction "C_2") (pintype "passive"))
    )
    (net (code "123") (name "Net-(T56-C)") (class "Default")
      (node (ref "JP56") (pin "1") (pinfunction "1_1") (pintype "passive"))
      (node (ref "T56") (pin "2") (pinfunction "C_2") (pintype "passive"))
    )
    (net (code "124") (name "unconnected-(IC7A-QH*-Pad9)") (class "Default")
      (node (ref "IC7") (pin "9") (pinfunction "QH*_9") (pintype "tri_state"))
    )
  )
)
